# schMapaSensorChassi.net
KiCad netlist of a schematic drawn in Altium Designer
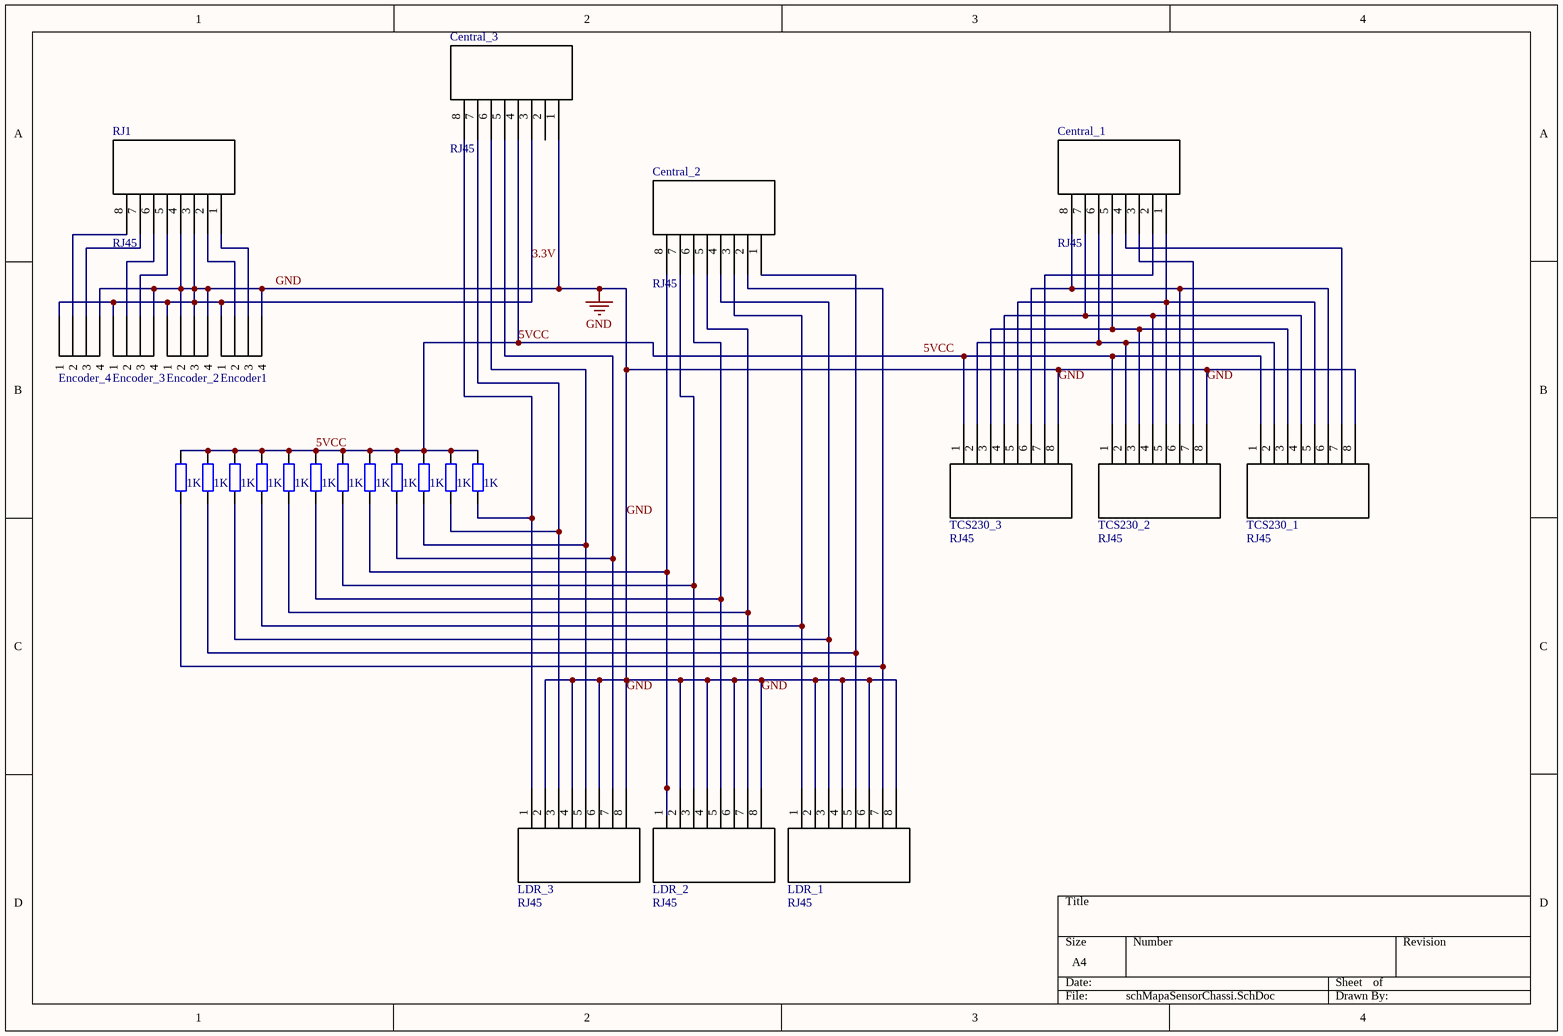
[diagram p0: schMapaSensorChassi.SchDoc]

(export (version "E")
  (design (tool "Eeschema 10.0.6"))
  (components
    (comp (ref "Central_1")
      (value "RJ45")
      (footprint "RJ45_90")
      (libsource (lib "Componentes_Open") (part "RJ45"))
    )
    (comp (ref "Central_2")
      (value "RJ45")
      (footprint "RJ45_90")
      (libsource (lib "Componentes_Open") (part "RJ45"))
    )
    (comp (ref "Central_3")
      (value "RJ45")
      (footprint "RJ45_90")
      (libsource (lib "Componentes_Open") (part "RJ45"))
    )
    (comp (ref "Encoder_1")
      (value "Encoder1")
      (footprint "4-vias")
      (libsource (lib "Componentes_Open") (part "KK4Vias"))
    )
    (comp (ref "Encoder_2")
      (value "Encoder_2")
      (footprint "4-vias")
      (libsource (lib "Componentes_Open") (part "KK4Vias"))
    )
    (comp (ref "Encoder_3")
      (value "Encoder_3")
      (footprint "4-vias")
      (libsource (lib "Componentes_Open") (part "KK4Vias"))
    )
    (comp (ref "K3")
      (value "Encoder_4")
      (footprint "4-vias")
      (libsource (lib "Componentes_Open") (part "KK4Vias"))
    )
    (comp (ref "LDR_1")
      (value "RJ45")
      (footprint "RJ45_Simples")
      (libsource (lib "Componentes_Open") (part "RJ45"))
    )
    (comp (ref "LDR_2")
      (value "RJ45")
      (footprint "RJ45_Simples")
      (libsource (lib "Componentes_Open") (part "RJ45"))
    )
    (comp (ref "LDR_3")
      (value "RJ45")
      (footprint "RJ45_Simples")
      (libsource (lib "Componentes_Open") (part "RJ45"))
    )
    (comp (ref "R1")
      (value "1K")
      (footprint "AXIAL-0.4")
      (description "Resistor")
      (fields (field (name "Comment") "Res2") (field (name "PUBLISHER") "Altium Limited"))
      (libsource (lib "Miscellaneous Devices") (part "Res2"))
    )
    (comp (ref "R2")
      (value "1K")
      (footprint "AXIAL-0.4")
      (description "Resistor")
      (fields (field (name "Comment") "Res2") (field (name "PUBLISHER") "Altium Limited"))
      (libsource (lib "Miscellaneous Devices") (part "Res2"))
    )
    (comp (ref "R3")
      (value "1K")
      (footprint "AXIAL-0.4")
      (description "Resistor")
      (fields (field (name "Comment") "Res2") (field (name "PUBLISHER") "Altium Limited"))
      (libsource (lib "Miscellaneous Devices") (part "Res2"))
    )
    (comp (ref "R4")
      (value "1K")
      (footprint "AXIAL-0.4")
      (description "Resistor")
      (fields (field (name "Comment") "Res2") (field (name "PUBLISHER") "Altium Limited"))
      (libsource (lib "Miscellaneous Devices") (part "Res2"))
    )
    (comp (ref "R5")
      (value "1K")
      (footprint "AXIAL-0.4")
      (description "Resistor")
      (fields (field (name "Comment") "Res2") (field (name "PUBLISHER") "Altium Limited"))
      (libsource (lib "Miscellaneous Devices") (part "Res2"))
    )
    (comp (ref "R6")
      (value "1K")
      (footprint "AXIAL-0.4")
      (description "Resistor")
      (fields (field (name "Comment") "Res2") (field (name "PUBLISHER") "Altium Limited"))
      (libsource (lib "Miscellaneous Devices") (part "Res2"))
    )
    (comp (ref "R7")
      (value "1K")
      (footprint "AXIAL-0.4")
      (description "Resistor")
      (fields (field (name "Comment") "Res2") (field (name "PUBLISHER") "Altium Limited"))
      (libsource (lib "Miscellaneous Devices") (part "Res2"))
    )
    (comp (ref "R8")
      (value "1K")
      (footprint "AXIAL-0.4")
      (description "Resistor")
      (fields (field (name "Comment") "Res2") (field (name "PUBLISHER") "Altium Limited"))
      (libsource (lib "Miscellaneous Devices") (part "Res2"))
    )
    (comp (ref "R9")
      (value "1K")
      (footprint "AXIAL-0.4")
      (description "Resistor")
      (fields (field (name "Comment") "Res2") (field (name "PUBLISHER") "Altium Limited"))
      (libsource (lib "Miscellaneous Devices") (part "Res2"))
    )
    (comp (ref "R10")
      (value "1K")
      (footprint "AXIAL-0.4")
      (description "Resistor")
      (fields (field (name "Comment") "Res2") (field (name "PUBLISHER") "Altium Limited"))
      (libsource (lib "Miscellaneous Devices") (part "Res2"))
    )
    (comp (ref "R11")
      (value "1K")
      (footprint "AXIAL-0.4")
      (description "Resistor")
      (fields (field (name "Comment") "Res2") (field (name "PUBLISHER") "Altium Limited"))
      (libsource (lib "Miscellaneous Devices") (part "Res2"))
    )
    (comp (ref "R12")
      (value "1K")
      (footprint "AXIAL-0.4")
      (description "Resistor")
      (fields (field (name "Comment") "Res2") (field (name "PUBLISHER") "Altium Limited"))
      (libsource (lib "Miscellaneous Devices") (part "Res2"))
    )
    (comp (ref "RJ1") (value "RJ45") (footprint "RJ45_90") (libsource (lib "Componentes_Open") (part "RJ45")))
    (comp (ref "TCS230_1")
      (value "RJ45")
      (footprint "RJ45_90")
      (libsource (lib "Componentes_Open") (part "RJ45"))
    )
    (comp (ref "TCS230_2")
      (value "RJ45")
      (footprint "RJ45_90")
      (libsource (lib "Componentes_Open") (part "RJ45"))
    )
    (comp (ref "TCS230_3")
      (value "RJ45")
      (footprint "RJ45_Simples")
      (libsource (lib "Componentes_Open") (part "RJ45"))
    )
  )
  (nets
    (net (code "1") (name "/5VCC") (class "Default")
      (node (ref "Central_3") (pin "4") (pinfunction "4_4") (pintype "passive"))
      (node (ref "R1") (pin "2") (pinfunction "2_2") (pintype "passive"))
      (node (ref "R10") (pin "2") (pinfunction "2_2") (pintype "passive"))
      (node (ref "R11") (pin "2") (pinfunction "2_2") (pintype "passive"))
      (node (ref "R12") (pin "2") (pinfunction "2_2") (pintype "passive"))
      (node (ref "R2") (pin "2") (pinfunction "2_2") (pintype "passive"))
      (node (ref "R3") (pin "2") (pinfunction "2_2") (pintype "passive"))
      (node (ref "R4") (pin "2") (pinfunction "2_2") (pintype "passive"))
      (node (ref "R5") (pin "2") (pinfunction "2_2") (pintype "passive"))
      (node (ref "R6") (pin "2") (pinfunction "2_2") (pintype "passive"))
      (node (ref "R7") (pin "2") (pinfunction "2_2") (pintype "passive"))
      (node (ref "R8") (pin "2") (pinfunction "2_2") (pintype "passive"))
      (node (ref "R9") (pin "2") (pinfunction "2_2") (pintype "passive"))
      (node (ref "TCS230_1") (pin "1") (pinfunction "9_1") (pintype "passive"))
      (node (ref "TCS230_2") (pin "1") (pinfunction "9_1") (pintype "passive"))
      (node (ref "TCS230_3") (pin "1") (pinfunction "9_1") (pintype "passive"))
    )
    (net (code "2") (name "GND") (class "Default")
      (node (ref "Central_3") (pin "1") (pinfunction "9_1") (pintype "passive"))
      (node (ref "Central_3") (pin "3") (pinfunction "3_3") (pintype "passive"))
      (node (ref "Encoder_1") (pin "1") (pinfunction "1_1") (pintype "passive"))
      (node (ref "Encoder_1") (pin "4") (pinfunction "4_4") (pintype "passive"))
      (node (ref "Encoder_2") (pin "1") (pinfunction "1_1") (pintype "passive"))
      (node (ref "Encoder_2") (pin "2") (pinfunction "2_2") (pintype "passive"))
      (node (ref "Encoder_2") (pin "3") (pinfunction "3_3") (pintype "passive"))
      (node (ref "Encoder_2") (pin "4") (pinfunction "4_4") (pintype "passive"))
      (node (ref "Encoder_3") (pin "1") (pinfunction "1_1") (pintype "passive"))
      (node (ref "Encoder_3") (pin "4") (pinfunction "4_4") (pintype "passive"))
      (node (ref "K3") (pin "1") (pinfunction "1_1") (pintype "passive"))
      (node (ref "K3") (pin "4") (pinfunction "4_4") (pintype "passive"))
      (node (ref "LDR_1") (pin "2") (pinfunction "2_2") (pintype "passive"))
      (node (ref "LDR_1") (pin "4") (pinfunction "4_4") (pintype "passive"))
      (node (ref "LDR_1") (pin "6") (pinfunction "6_6") (pintype "passive"))
      (node (ref "LDR_1") (pin "8") (pinfunction "8_8") (pintype "passive"))
      (node (ref "LDR_2") (pin "2") (pinfunction "2_2") (pintype "passive"))
      (node (ref "LDR_2") (pin "4") (pinfunction "4_4") (pintype "passive"))
      (node (ref "LDR_2") (pin "6") (pinfunction "6_6") (pintype "passive"))
      (node (ref "LDR_2") (pin "8") (pinfunction "8_8") (pintype "passive"))
      (node (ref "LDR_3") (pin "2") (pinfunction "2_2") (pintype "passive"))
      (node (ref "LDR_3") (pin "4") (pinfunction "4_4") (pintype "passive"))
      (node (ref "LDR_3") (pin "6") (pinfunction "6_6") (pintype "passive"))
      (node (ref "LDR_3") (pin "8") (pinfunction "8_8") (pintype "passive"))
      (node (ref "RJ1") (pin "3") (pinfunction "3_3") (pintype "passive"))
      (node (ref "RJ1") (pin "4") (pinfunction "4_4") (pintype "passive"))
      (node (ref "TCS230_1") (pin "8") (pinfunction "8_8") (pintype "passive"))
      (node (ref "TCS230_2") (pin "8") (pinfunction "8_8") (pintype "passive"))
      (node (ref "TCS230_3") (pin "8") (pinfunction "8_8") (pintype "passive"))
    )
    (net (code "3") (name "Net-(Central_1-9)") (class "Default")
      (node (ref "Central_1") (pin "1") (pinfunction "9_1") (pintype "passive"))
      (node (ref "TCS230_1") (pin "5") (pinfunction "5_5") (pintype "passive"))
      (node (ref "TCS230_2") (pin "5") (pinfunction "5_5") (pintype "passive"))
      (node (ref "TCS230_3") (pin "5") (pinfunction "5_5") (pintype "passive"))
    )
    (net (code "4") (name "Net-(Central_1-Pad2)") (class "Default")
      (node (ref "Central_1") (pin "2") (pinfunction "2_2") (pintype "passive"))
      (node (ref "TCS230_3") (pin "7") (pinfunction "7_7") (pintype "passive"))
    )
    (net (code "5") (name "Net-(Central_1-Pad3)") (class "Default")
      (node (ref "Central_1") (pin "3") (pinfunction "3_3") (pintype "passive"))
      (node (ref "TCS230_2") (pin "7") (pinfunction "7_7") (pintype "passive"))
    )
    (net (code "6") (name "Net-(Central_1-Pad4)") (class "Default")
      (node (ref "Central_1") (pin "4") (pinfunction "4_4") (pintype "passive"))
      (node (ref "TCS230_1") (pin "7") (pinfunction "7_7") (pintype "passive"))
    )
    (net (code "7") (name "Net-(Central_1-Pad5)") (class "Default")
      (node (ref "Central_1") (pin "5") (pinfunction "5_5") (pintype "passive"))
      (node (ref "TCS230_1") (pin "3") (pinfunction "3_3") (pintype "passive"))
      (node (ref "TCS230_2") (pin "3") (pinfunction "3_3") (pintype "passive"))
      (node (ref "TCS230_3") (pin "3") (pinfunction "3_3") (pintype "passive"))
    )
    (net (code "8") (name "Net-(Central_1-Pad6)") (class "Default")
      (node (ref "Central_1") (pin "6") (pinfunction "6_6") (pintype "passive"))
      (node (ref "TCS230_1") (pin "2") (pinfunction "2_2") (pintype "passive"))
      (node (ref "TCS230_2") (pin "2") (pinfunction "2_2") (pintype "passive"))
      (node (ref "TCS230_3") (pin "2") (pinfunction "2_2") (pintype "passive"))
    )
    (net (code "9") (name "Net-(Central_1-Pad7)") (class "Default")
      (node (ref "Central_1") (pin "7") (pinfunction "7_7") (pintype "passive"))
      (node (ref "TCS230_1") (pin "4") (pinfunction "4_4") (pintype "passive"))
      (node (ref "TCS230_2") (pin "4") (pinfunction "4_4") (pintype "passive"))
      (node (ref "TCS230_3") (pin "4") (pinfunction "4_4") (pintype "passive"))
    )
    (net (code "10") (name "Net-(Central_1-Pad8)") (class "Default")
      (node (ref "Central_1") (pin "8") (pinfunction "8_8") (pintype "passive"))
      (node (ref "TCS230_1") (pin "6") (pinfunction "6_6") (pintype "passive"))
      (node (ref "TCS230_2") (pin "6") (pinfunction "6_6") (pintype "passive"))
      (node (ref "TCS230_3") (pin "6") (pinfunction "6_6") (pintype "passive"))
    )
    (net (code "11") (name "Net-(Central_2-9)") (class "Default")
      (node (ref "Central_2") (pin "1") (pinfunction "9_1") (pintype "passive"))
      (node (ref "LDR_1") (pin "5") (pinfunction "5_5") (pintype "passive"))
      (node (ref "R2") (pin "1") (pinfunction "1_1") (pintype "passive"))
    )
    (net (code "12") (name "Net-(Central_2-Pad2)") (class "Default")
      (node (ref "Central_2") (pin "2") (pinfunction "2_2") (pintype "passive"))
      (node (ref "LDR_1") (pin "7") (pinfunction "7_7") (pintype "passive"))
      (node (ref "R1") (pin "1") (pinfunction "1_1") (pintype "passive"))
    )
    (net (code "13") (name "Net-(Central_2-Pad4)") (class "Default")
      (node (ref "Central_2") (pin "4") (pinfunction "4_4") (pintype "passive"))
      (node (ref "LDR_1") (pin "3") (pinfunction "3_3") (pintype "passive"))
      (node (ref "R3") (pin "1") (pinfunction "1_1") (pintype "passive"))
    )
    (net (code "14") (name "Net-(Central_2-Pad5)") (class "Default")
      (node (ref "Central_2") (pin "5") (pinfunction "5_5") (pintype "passive"))
      (node (ref "LDR_2") (pin "7") (pinfunction "7_7") (pintype "passive"))
      (node (ref "R5") (pin "1") (pinfunction "1_1") (pintype "passive"))
    )
    (net (code "15") (name "Net-(Central_2-Pad6)") (class "Default")
      (node (ref "Central_2") (pin "6") (pinfunction "6_6") (pintype "passive"))
      (node (ref "LDR_2") (pin "5") (pinfunction "5_5") (pintype "passive"))
      (node (ref "R6") (pin "1") (pinfunction "1_1") (pintype "passive"))
    )
    (net (code "16") (name "Net-(Central_2-Pad7)") (class "Default")
      (node (ref "Central_2") (pin "7") (pinfunction "7_7") (pintype "passive"))
      (node (ref "LDR_2") (pin "3") (pinfunction "3_3") (pintype "passive"))
      (node (ref "R7") (pin "1") (pinfunction "1_1") (pintype "passive"))
    )
    (net (code "17") (name "Net-(Central_3-Pad5)") (class "Default")
      (node (ref "Central_3") (pin "5") (pinfunction "5_5") (pintype "passive"))
      (node (ref "LDR_3") (pin "7") (pinfunction "7_7") (pintype "passive"))
      (node (ref "R9") (pin "1") (pinfunction "1_1") (pintype "passive"))
    )
    (net (code "18") (name "Net-(Central_3-Pad6)") (class "Default")
      (node (ref "Central_3") (pin "6") (pinfunction "6_6") (pintype "passive"))
      (node (ref "LDR_3") (pin "5") (pinfunction "5_5") (pintype "passive"))
      (node (ref "R10") (pin "1") (pinfunction "1_1") (pintype "passive"))
    )
    (net (code "19") (name "Net-(Central_3-Pad7)") (class "Default")
      (node (ref "Central_3") (pin "7") (pinfunction "7_7") (pintype "passive"))
      (node (ref "LDR_3") (pin "3") (pinfunction "3_3") (pintype "passive"))
      (node (ref "R11") (pin "1") (pinfunction "1_1") (pintype "passive"))
    )
    (net (code "20") (name "Net-(Encoder_1-Pad2)") (class "Default")
      (node (ref "Encoder_1") (pin "2") (pinfunction "2_2") (pintype "passive"))
      (node (ref "RJ1") (pin "2") (pinfunction "2_2") (pintype "passive"))
    )
    (net (code "21") (name "Net-(Encoder_3-Pad2)") (class "Default")
      (node (ref "Encoder_3") (pin "2") (pinfunction "2_2") (pintype "passive"))
      (node (ref "RJ1") (pin "6") (pinfunction "6_6") (pintype "passive"))
    )
    (net (code "22") (name "Net-(Encoder_3-Pad3)") (class "Default")
      (node (ref "Encoder_3") (pin "3") (pinfunction "3_3") (pintype "passive"))
      (node (ref "RJ1") (pin "5") (pinfunction "5_5") (pintype "passive"))
    )
    (net (code "23") (name "Net-(K3-Pad2)") (class "Default")
      (node (ref "K3") (pin "2") (pinfunction "2_2") (pintype "passive"))
      (node (ref "RJ1") (pin "8") (pinfunction "8_8") (pintype "passive"))
    )
    (net (code "24") (name "Net-(K3-Pad3)") (class "Default")
      (node (ref "K3") (pin "3") (pinfunction "3_3") (pintype "passive"))
      (node (ref "RJ1") (pin "7") (pinfunction "7_7") (pintype "passive"))
    )
    (net (code "25") (name "Net-(LDR_1-9)") (class "Default")
      (node (ref "Central_2") (pin "3") (pinfunction "3_3") (pintype "passive"))
      (node (ref "LDR_1") (pin "1") (pinfunction "9_1") (pintype "passive"))
      (node (ref "R4") (pin "1") (pinfunction "1_1") (pintype "passive"))
    )
    (net (code "26") (name "Net-(LDR_2-9)") (class "Default")
      (node (ref "Central_2") (pin "8") (pinfunction "8_8") (pintype "passive"))
      (node (ref "LDR_2") (pin "1") (pinfunction "9_1") (pintype "passive"))
      (node (ref "R8") (pin "1") (pinfunction "1_1") (pintype "passive"))
    )
    (net (code "27") (name "Net-(LDR_3-9)") (class "Default")
      (node (ref "Central_3") (pin "8") (pinfunction "8_8") (pintype "passive"))
      (node (ref "LDR_3") (pin "1") (pinfunction "9_1") (pintype "passive"))
      (node (ref "R12") (pin "1") (pinfunction "1_1") (pintype "passive"))
    )
    (net (code "28") (name "Net-(RJ1-9)") (class "Default")
      (node (ref "Encoder_1") (pin "3") (pinfunction "3_3") (pintype "passive"))
      (node (ref "RJ1") (pin "1") (pinfunction "9_1") (pintype "passive"))
    )
    (net (code "29") (name "unconnected-(Central_3-Pad2)") (class "Default")
      (node (ref "Central_3") (pin "2") (pinfunction "2_2") (pintype "passive"))
    )
  )
)
